# AD5941_testboard.net
KiCad netlist of a schematic drawn in EAGLE
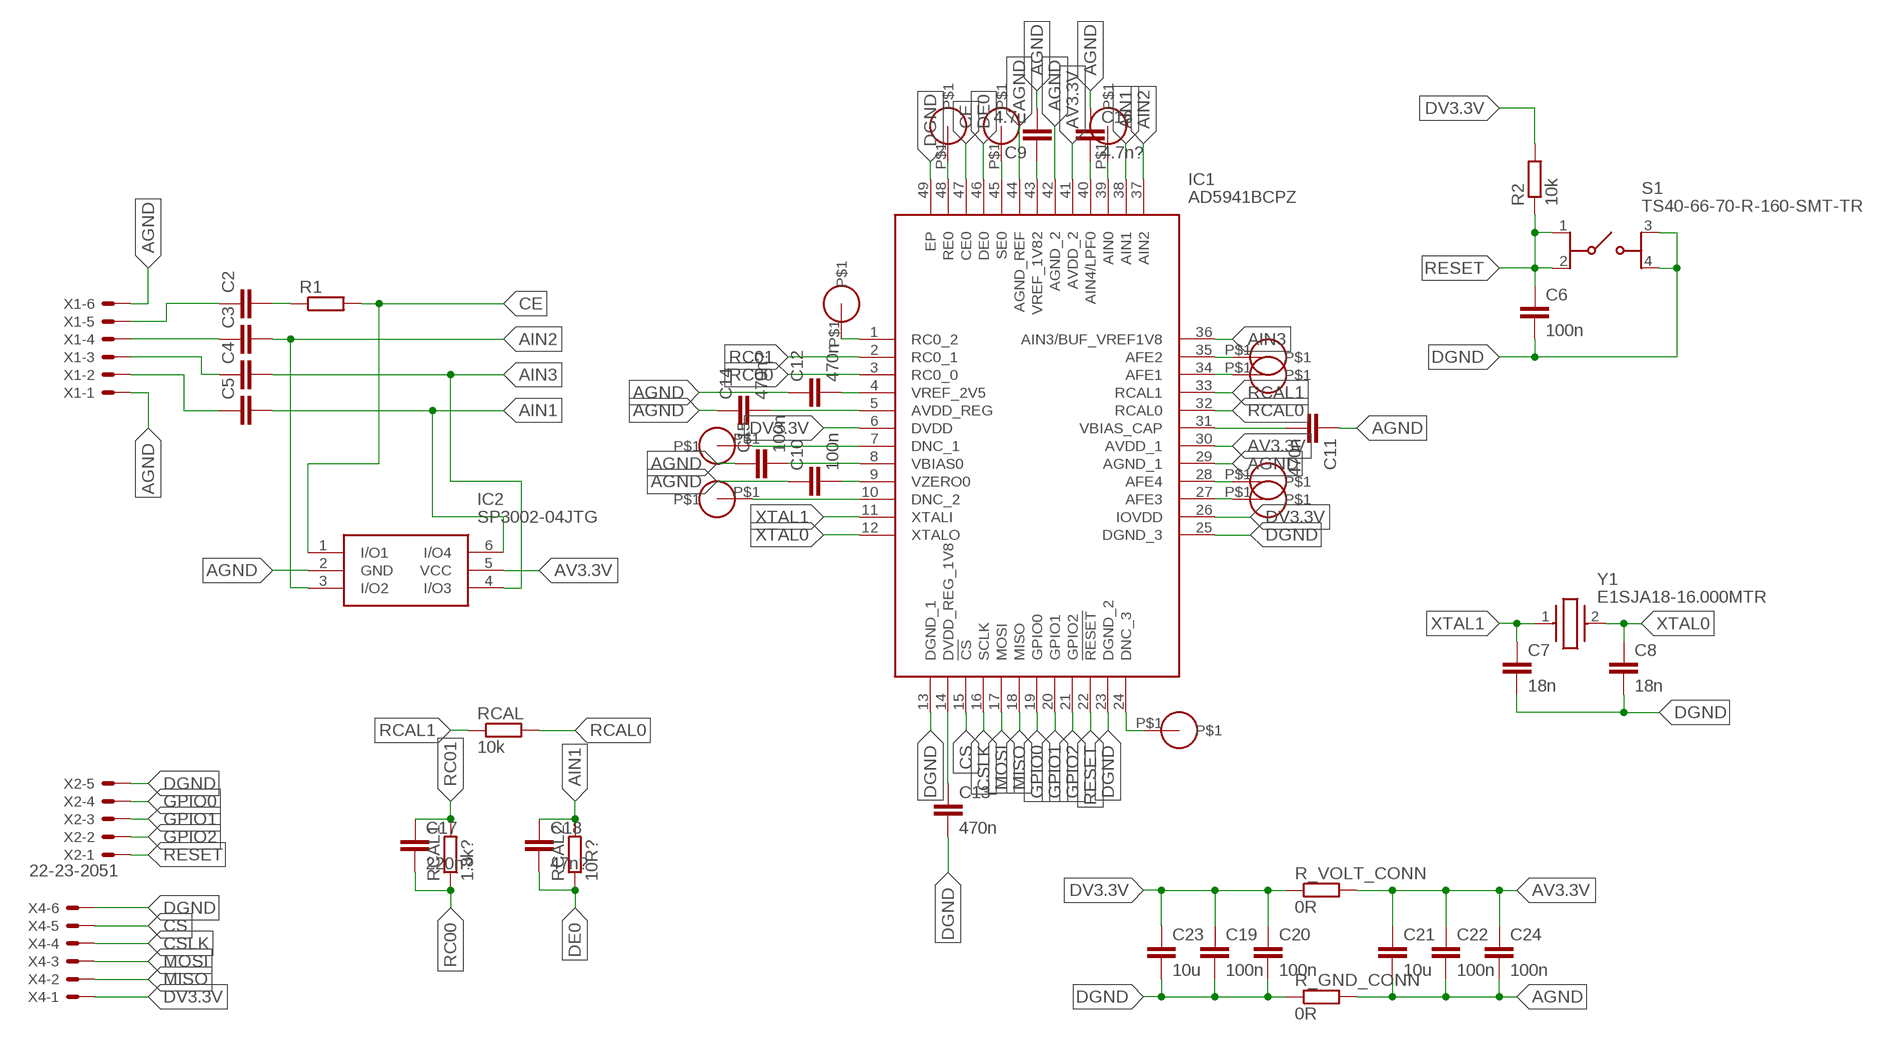
[diagram p0: schematic, sheet 1]

(export (version "E")
  (design (tool "Eeschema 10.0.6"))
  (components
    (comp (ref "C2")
      (value "C-EUC0805")
      (footprint "eagle-import:C0805")
      (libsource (lib "eagle-import") (part "C-EUC0805"))
    )
    (comp (ref "C3")
      (value "C-EUC0805")
      (footprint "eagle-import:C0805")
      (libsource (lib "eagle-import") (part "C-EUC0805"))
    )
    (comp (ref "C4")
      (value "C-EUC0805")
      (footprint "eagle-import:C0805")
      (libsource (lib "eagle-import") (part "C-EUC0805"))
    )
    (comp (ref "C5")
      (value "C-EUC0805")
      (footprint "eagle-import:C0805")
      (libsource (lib "eagle-import") (part "C-EUC0805"))
    )
    (comp (ref "C6")
      (value "100n")
      (footprint "eagle-import:C0805")
      (libsource (lib "eagle-import") (part "C-EUC0805"))
    )
    (comp (ref "C7")
      (value "18n")
      (footprint "eagle-import:C0805")
      (libsource (lib "eagle-import") (part "C-EUC0805"))
    )
    (comp (ref "C8")
      (value "18n")
      (footprint "eagle-import:C0805")
      (libsource (lib "eagle-import") (part "C-EUC0805"))
    )
    (comp (ref "C9")
      (value "4.7u")
      (footprint "eagle-import:C0805")
      (libsource (lib "eagle-import") (part "C-EUC0805"))
    )
    (comp (ref "C10")
      (value "100n")
      (footprint "eagle-import:C0805")
      (libsource (lib "eagle-import") (part "C-EUC0805"))
    )
    (comp (ref "C11")
      (value "470n")
      (footprint "eagle-import:C0805")
      (libsource (lib "eagle-import") (part "C-EUC0805"))
    )
    (comp (ref "C12")
      (value "470n")
      (footprint "eagle-import:C0805")
      (libsource (lib "eagle-import") (part "C-EUC0805"))
    )
    (comp (ref "C13")
      (value "470n")
      (footprint "eagle-import:C0805")
      (libsource (lib "eagle-import") (part "C-EUC0805"))
    )
    (comp (ref "C14")
      (value "470n?")
      (footprint "eagle-import:C0805")
      (libsource (lib "eagle-import") (part "C-EUC0805"))
    )
    (comp (ref "C15")
      (value "100n")
      (footprint "eagle-import:C0805")
      (libsource (lib "eagle-import") (part "C-EUC0805"))
    )
    (comp (ref "C16")
      (value "4.7n?")
      (footprint "eagle-import:C0805")
      (libsource (lib "eagle-import") (part "C-EUC0805"))
    )
    (comp (ref "C17")
      (value "220n?")
      (footprint "eagle-import:C0805")
      (libsource (lib "eagle-import") (part "C-EUC0805"))
    )
    (comp (ref "C18")
      (value "47n?")
      (footprint "eagle-import:C0805")
      (libsource (lib "eagle-import") (part "C-EUC0805"))
    )
    (comp (ref "C19")
      (value "100n")
      (footprint "eagle-import:C0805")
      (libsource (lib "eagle-import") (part "C-EUC0805"))
    )
    (comp (ref "C20")
      (value "100n")
      (footprint "eagle-import:C0805")
      (libsource (lib "eagle-import") (part "C-EUC0805"))
    )
    (comp (ref "C21")
      (value "10u")
      (footprint "eagle-import:C0805")
      (libsource (lib "eagle-import") (part "C-EUC0805"))
    )
    (comp (ref "C22")
      (value "100n")
      (footprint "eagle-import:C0805")
      (libsource (lib "eagle-import") (part "C-EUC0805"))
    )
    (comp (ref "C23")
      (value "10u")
      (footprint "eagle-import:C0805")
      (libsource (lib "eagle-import") (part "C-EUC0805"))
    )
    (comp (ref "C24")
      (value "100n")
      (footprint "eagle-import:C0805")
      (libsource (lib "eagle-import") (part "C-EUC0805"))
    )
    (comp (ref "IC1")
      (value "AD5941BCPZ")
      (footprint "eagle-import:QFN50P700X700X80-49N")
      (fields (field (name "MOUSER_PART_NUMBER") "584-AD5941BCPZ"))
      (libsource (lib "eagle-import") (part "AD5941BCPZ"))
    )
    (comp (ref "IC2")
      (value "SP3002-04JTG")
      (footprint "eagle-import:SOT65P220X110-6N")
      (fields (field (name "MOUSER_PART_NUMBER") "576-SP3002-04JTG"))
      (libsource (lib "eagle-import") (part "SP3002-04JTG"))
    )
    (comp (ref "R1")
      (value "R-EU_R0603")
      (footprint "eagle-import:R0603")
      (libsource (lib "eagle-import") (part "R-EU_R0603"))
    )
    (comp (ref "R2")
      (value "10k")
      (footprint "eagle-import:R0603")
      (libsource (lib "eagle-import") (part "R-EU_R0603"))
    )
    (comp (ref "RCAL")
      (value "10k")
      (footprint "eagle-import:R0603")
      (libsource (lib "eagle-import") (part "R-EU_R0603"))
    )
    (comp (ref "RCAL1")
      (value "1.8k?")
      (footprint "eagle-import:R0603")
      (libsource (lib "eagle-import") (part "R-EU_R0603"))
    )
    (comp (ref "RCAL2")
      (value "10R?")
      (footprint "eagle-import:R0603")
      (libsource (lib "eagle-import") (part "R-EU_R0603"))
    )
    (comp (ref "R_GND_CONN")
      (value "0R")
      (footprint "eagle-import:R0603")
      (libsource (lib "eagle-import") (part "R-EU_R0603"))
    )
    (comp (ref "R_VOLT_CONN")
      (value "0R")
      (footprint "eagle-import:R0603")
      (libsource (lib "eagle-import") (part "R-EU_R0603"))
    )
    (comp (ref "S1")
      (value "TS40-66-70-R-160-SMT-TR")
      (footprint "eagle-import:TS406670R160SMTTR")
      (libsource (lib "eagle-import") (part "TS40-66-70-R-160-SMT-TR"))
    )
    (comp (ref "U$1")
      (value "1XPIN+HOLE")
      (footprint "eagle-import:1XPIN+HOLE")
      (libsource (lib "eagle-import") (part "1XPIN+HOLE"))
    )
    (comp (ref "U$2")
      (value "1XPIN+HOLE")
      (footprint "eagle-import:1XPIN+HOLE")
      (libsource (lib "eagle-import") (part "1XPIN+HOLE"))
    )
    (comp (ref "U$3")
      (value "1XPIN+HOLE")
      (footprint "eagle-import:1XPIN+HOLE")
      (libsource (lib "eagle-import") (part "1XPIN+HOLE"))
    )
    (comp (ref "U$4")
      (value "1XPIN+HOLE")
      (footprint "eagle-import:1XPIN+HOLE")
      (libsource (lib "eagle-import") (part "1XPIN+HOLE"))
    )
    (comp (ref "U$5")
      (value "1XPIN+HOLE")
      (footprint "eagle-import:1XPIN+HOLE")
      (libsource (lib "eagle-import") (part "1XPIN+HOLE"))
    )
    (comp (ref "U$6")
      (value "1XPIN+HOLE")
      (footprint "eagle-import:1XPIN+HOLE")
      (libsource (lib "eagle-import") (part "1XPIN+HOLE"))
    )
    (comp (ref "U$7")
      (value "1XPIN+HOLE")
      (footprint "eagle-import:1XPIN+HOLE")
      (libsource (lib "eagle-import") (part "1XPIN+HOLE"))
    )
    (comp (ref "U$8")
      (value "1XPIN+HOLE")
      (footprint "eagle-import:1XPIN+HOLE")
      (libsource (lib "eagle-import") (part "1XPIN+HOLE"))
    )
    (comp (ref "U$9")
      (value "1XPIN+HOLE")
      (footprint "eagle-import:1XPIN+HOLE")
      (libsource (lib "eagle-import") (part "1XPIN+HOLE"))
    )
    (comp (ref "U$10")
      (value "1XPIN+HOLE")
      (footprint "eagle-import:1XPIN+HOLE")
      (libsource (lib "eagle-import") (part "1XPIN+HOLE"))
    )
    (comp (ref "U$11")
      (value "1XPIN+HOLE")
      (footprint "eagle-import:1XPIN+HOLE")
      (libsource (lib "eagle-import") (part "1XPIN+HOLE"))
    )
    (comp (ref "X1")
      (value "22-23-2061")
      (footprint "eagle-import:22-23-2061")
      (fields (field (name "MF") "MOLEX"))
      (libsource (lib "eagle-import") (part "22-23-2061"))
    )
    (comp (ref "X2")
      (value "22-23-2051")
      (footprint "eagle-import:22-23-2051")
      (fields (field (name "MF") "MOLEX"))
      (libsource (lib "eagle-import") (part "22-23-2051"))
    )
    (comp (ref "X4")
      (value "22-23-2061")
      (footprint "eagle-import:22-23-2061")
      (fields (field (name "MF") "MOLEX"))
      (libsource (lib "eagle-import") (part "22-23-2061"))
    )
    (comp (ref "Y1")
      (value "E1SJA18-16.000MTR")
      (footprint "eagle-import:E1SJA1816000MTR")
      (fields (field (name "MOUSER_PART_NUMBER") "815-E1SJA1816000MTR"))
      (libsource (lib "eagle-import") (part "E1SJA18-16.000MTR"))
    )
  )
  (nets
    (net (code "1") (name "AGND") (class "Default")
      (node (ref "C10") (pin "1") (pinfunction "1_1") (pintype "passive"))
      (node (ref "C11") (pin "1") (pinfunction "1_1") (pintype "passive"))
      (node (ref "C12") (pin "1") (pinfunction "1_1") (pintype "passive"))
      (node (ref "C14") (pin "1") (pinfunction "1_1") (pintype "passive"))
      (node (ref "C15") (pin "1") (pinfunction "1_1") (pintype "passive"))
      (node (ref "C16") (pin "1") (pinfunction "1_1") (pintype "passive"))
      (node (ref "C21") (pin "2") (pinfunction "2_2") (pintype "passive"))
      (node (ref "C22") (pin "2") (pinfunction "2_2") (pintype "passive"))
      (node (ref "C24") (pin "2") (pinfunction "2_2") (pintype "passive"))
      (node (ref "C9") (pin "2") (pinfunction "2_2") (pintype "passive"))
      (node (ref "IC1") (pin "29") (pinfunction "AGND_1_29") (pintype "bidirectional"))
      (node (ref "IC1") (pin "42") (pinfunction "AGND_2_42") (pintype "bidirectional"))
      (node (ref "IC1") (pin "44") (pinfunction "AGND_REF_44") (pintype "bidirectional"))
      (node (ref "IC2") (pin "2") (pinfunction "GND_2") (pintype "bidirectional"))
      (node (ref "R_GND_CONN") (pin "2") (pinfunction "2_2") (pintype "passive"))
      (node (ref "X1") (pin "1") (pinfunction "S_1") (pintype "passive"))
      (node (ref "X1") (pin "6") (pinfunction "S_6") (pintype "passive"))
    )
    (net (code "2") (name "AIN1") (class "Default")
      (node (ref "C18") (pin "1") (pinfunction "1_1") (pintype "passive"))
      (node (ref "C5") (pin "2") (pinfunction "2_2") (pintype "passive"))
      (node (ref "IC1") (pin "38") (pinfunction "AIN1_38") (pintype "bidirectional"))
      (node (ref "IC2") (pin "6") (pinfunction "I/O4_6") (pintype "bidirectional"))
      (node (ref "RCAL2") (pin "2") (pinfunction "2_2") (pintype "passive"))
    )
    (net (code "3") (name "AIN2") (class "Default")
      (node (ref "C3") (pin "2") (pinfunction "2_2") (pintype "passive"))
      (node (ref "IC1") (pin "37") (pinfunction "AIN2_37") (pintype "bidirectional"))
      (node (ref "IC2") (pin "3") (pinfunction "I/O2_3") (pintype "bidirectional"))
    )
    (net (code "4") (name "AIN3") (class "Default")
      (node (ref "C4") (pin "2") (pinfunction "2_2") (pintype "passive"))
      (node (ref "IC1") (pin "36") (pinfunction "AIN3/BUF_VREF1V8_36") (pintype "bidirectional"))
      (node (ref "IC2") (pin "4") (pinfunction "I/O3_4") (pintype "bidirectional"))
    )
    (net (code "5") (name "AV3.3V") (class "Default")
      (node (ref "C21") (pin "1") (pinfunction "1_1") (pintype "passive"))
      (node (ref "C22") (pin "1") (pinfunction "1_1") (pintype "passive"))
      (node (ref "C24") (pin "1") (pinfunction "1_1") (pintype "passive"))
      (node (ref "IC1") (pin "30") (pinfunction "AVDD_1_30") (pintype "bidirectional"))
      (node (ref "IC1") (pin "41") (pinfunction "AVDD_2_41") (pintype "bidirectional"))
      (node (ref "IC2") (pin "5") (pinfunction "VCC_5") (pintype "bidirectional"))
      (node (ref "R_VOLT_CONN") (pin "2") (pinfunction "2_2") (pintype "passive"))
    )
    (net (code "6") (name "CE") (class "Default")
      (node (ref "IC1") (pin "47") (pinfunction "CE0_47") (pintype "bidirectional"))
      (node (ref "IC2") (pin "1") (pinfunction "I/O1_1") (pintype "bidirectional"))
      (node (ref "R1") (pin "2") (pinfunction "2_2") (pintype "passive"))
    )
    (net (code "7") (name "CS") (class "Default")
      (node (ref "IC1") (pin "15") (pinfunction "~{CS}_15") (pintype "bidirectional"))
      (node (ref "X4") (pin "5") (pinfunction "S_5") (pintype "passive"))
    )
    (net (code "8") (name "CSLK") (class "Default")
      (node (ref "IC1") (pin "16") (pinfunction "SCLK_16") (pintype "bidirectional"))
      (node (ref "X4") (pin "4") (pinfunction "S_4") (pintype "passive"))
    )
    (net (code "9") (name "DE0") (class "Default")
      (node (ref "C18") (pin "2") (pinfunction "2_2") (pintype "passive"))
      (node (ref "IC1") (pin "46") (pinfunction "DE0_46") (pintype "bidirectional"))
      (node (ref "RCAL2") (pin "1") (pinfunction "1_1") (pintype "passive"))
    )
    (net (code "10") (name "DGND") (class "Default")
      (node (ref "C13") (pin "2") (pinfunction "2_2") (pintype "passive"))
      (node (ref "C19") (pin "2") (pinfunction "2_2") (pintype "passive"))
      (node (ref "C20") (pin "2") (pinfunction "2_2") (pintype "passive"))
      (node (ref "C23") (pin "2") (pinfunction "2_2") (pintype "passive"))
      (node (ref "C6") (pin "2") (pinfunction "2_2") (pintype "passive"))
      (node (ref "C7") (pin "2") (pinfunction "2_2") (pintype "passive"))
      (node (ref "C8") (pin "2") (pinfunction "2_2") (pintype "passive"))
      (node (ref "IC1") (pin "13") (pinfunction "DGND_1_13") (pintype "bidirectional"))
      (node (ref "IC1") (pin "23") (pinfunction "DGND_2_23") (pintype "bidirectional"))
      (node (ref "IC1") (pin "25") (pinfunction "DGND_3_25") (pintype "bidirectional"))
      (node (ref "IC1") (pin "49") (pinfunction "EP_49") (pintype "bidirectional"))
      (node (ref "R_GND_CONN") (pin "1") (pinfunction "1_1") (pintype "passive"))
      (node (ref "S1") (pin "3") (pinfunction "NO_1_3") (pintype "bidirectional"))
      (node (ref "S1") (pin "4") (pinfunction "NO_2_4") (pintype "bidirectional"))
      (node (ref "X2") (pin "5") (pinfunction "S_5") (pintype "passive"))
      (node (ref "X4") (pin "6") (pinfunction "S_6") (pintype "passive"))
    )
    (net (code "11") (name "DV3.3V") (class "Default")
      (node (ref "C19") (pin "1") (pinfunction "1_1") (pintype "passive"))
      (node (ref "C20") (pin "1") (pinfunction "1_1") (pintype "passive"))
      (node (ref "C23") (pin "1") (pinfunction "1_1") (pintype "passive"))
      (node (ref "IC1") (pin "26") (pinfunction "IOVDD_26") (pintype "bidirectional"))
      (node (ref "IC1") (pin "6") (pinfunction "DVDD_6") (pintype "bidirectional"))
      (node (ref "R2") (pin "2") (pinfunction "2_2") (pintype "passive"))
      (node (ref "R_VOLT_CONN") (pin "1") (pinfunction "1_1") (pintype "passive"))
      (node (ref "X4") (pin "1") (pinfunction "S_1") (pintype "passive"))
    )
    (net (code "12") (name "GPIO0") (class "Default")
      (node (ref "IC1") (pin "19") (pinfunction "GPIO0_19") (pintype "bidirectional"))
      (node (ref "X2") (pin "4") (pinfunction "S_4") (pintype "passive"))
    )
    (net (code "13") (name "GPIO1") (class "Default")
      (node (ref "IC1") (pin "20") (pinfunction "GPIO1_20") (pintype "bidirectional"))
      (node (ref "X2") (pin "3") (pinfunction "S_3") (pintype "passive"))
    )
    (net (code "14") (name "GPIO2") (class "Default")
      (node (ref "IC1") (pin "21") (pinfunction "GPIO2_21") (pintype "bidirectional"))
      (node (ref "X2") (pin "2") (pinfunction "S_2") (pintype "passive"))
    )
    (net (code "15") (name "MISO") (class "Default")
      (node (ref "IC1") (pin "18") (pinfunction "MISO_18") (pintype "bidirectional"))
      (node (ref "X4") (pin "2") (pinfunction "S_2") (pintype "passive"))
    )
    (net (code "16") (name "MOSI") (class "Default")
      (node (ref "IC1") (pin "17") (pinfunction "MOSI_17") (pintype "bidirectional"))
      (node (ref "X4") (pin "3") (pinfunction "S_3") (pintype "passive"))
    )
    (net (code "17") (name "Net-(C2-Pad2)") (class "Default")
      (node (ref "C2") (pin "2") (pinfunction "2_2") (pintype "passive"))
      (node (ref "R1") (pin "1") (pinfunction "1_1") (pintype "passive"))
    )
    (net (code "18") (name "Net-(IC1-AFE1)") (class "Default")
      (node (ref "IC1") (pin "34") (pinfunction "AFE1_34") (pintype "bidirectional"))
      (node (ref "U$8") (pin "P$1") (pinfunction "P$1_P$1") (pintype "bidirectional"))
    )
    (net (code "19") (name "Net-(IC1-AFE2)") (class "Default")
      (node (ref "IC1") (pin "35") (pinfunction "AFE2_35") (pintype "bidirectional"))
      (node (ref "U$7") (pin "P$1") (pinfunction "P$1_P$1") (pintype "bidirectional"))
    )
    (net (code "20") (name "Net-(IC1-AFE3)") (class "Default")
      (node (ref "IC1") (pin "27") (pinfunction "AFE3_27") (pintype "bidirectional"))
      (node (ref "U$9") (pin "P$1") (pinfunction "P$1_P$1") (pintype "bidirectional"))
    )
    (net (code "21") (name "Net-(IC1-AFE4)") (class "Default")
      (node (ref "IC1") (pin "28") (pinfunction "AFE4_28") (pintype "bidirectional"))
      (node (ref "U$10") (pin "P$1") (pinfunction "P$1_P$1") (pintype "bidirectional"))
    )
    (net (code "22") (name "Net-(IC1-AIN0)") (class "Default")
      (node (ref "IC1") (pin "39") (pinfunction "AIN0_39") (pintype "bidirectional"))
      (node (ref "U$6") (pin "P$1") (pinfunction "P$1_P$1") (pintype "bidirectional"))
    )
    (net (code "23") (name "Net-(IC1-AIN4{slash}LPF0)") (class "Default")
      (node (ref "C16") (pin "2") (pinfunction "2_2") (pintype "passive"))
      (node (ref "IC1") (pin "40") (pinfunction "AIN4/LPF0_40") (pintype "bidirectional"))
    )
    (net (code "24") (name "Net-(IC1-AVDD_REG)") (class "Default")
      (node (ref "C14") (pin "2") (pinfunction "2_2") (pintype "passive"))
      (node (ref "IC1") (pin "5") (pinfunction "AVDD_REG_5") (pintype "bidirectional"))
    )
    (net (code "25") (name "Net-(IC1-DNC_1)") (class "Default")
      (node (ref "IC1") (pin "7") (pinfunction "DNC_1_7") (pintype "bidirectional"))
      (node (ref "U$11") (pin "P$1") (pinfunction "P$1_P$1") (pintype "bidirectional"))
    )
    (net (code "26") (name "Net-(IC1-DNC_2)") (class "Default")
      (node (ref "IC1") (pin "10") (pinfunction "DNC_2_10") (pintype "bidirectional"))
      (node (ref "U$3") (pin "P$1") (pinfunction "P$1_P$1") (pintype "bidirectional"))
    )
    (net (code "27") (name "Net-(IC1-DNC_3)") (class "Default")
      (node (ref "IC1") (pin "24") (pinfunction "DNC_3_24") (pintype "bidirectional"))
      (node (ref "U$1") (pin "P$1") (pinfunction "P$1_P$1") (pintype "bidirectional"))
    )
    (net (code "28") (name "Net-(IC1-DVDD_REG_1V8)") (class "Default")
      (node (ref "C13") (pin "1") (pinfunction "1_1") (pintype "passive"))
      (node (ref "IC1") (pin "14") (pinfunction "DVDD_REG_1V8_14") (pintype "bidirectional"))
    )
    (net (code "29") (name "Net-(IC1-RC0_2)") (class "Default")
      (node (ref "IC1") (pin "1") (pinfunction "RC0_2_1") (pintype "bidirectional"))
      (node (ref "U$2") (pin "P$1") (pinfunction "P$1_P$1") (pintype "bidirectional"))
    )
    (net (code "30") (name "Net-(IC1-RE0)") (class "Default")
      (node (ref "IC1") (pin "48") (pinfunction "RE0_48") (pintype "bidirectional"))
      (node (ref "U$4") (pin "P$1") (pinfunction "P$1_P$1") (pintype "bidirectional"))
    )
    (net (code "31") (name "Net-(IC1-SE0)") (class "Default")
      (node (ref "IC1") (pin "45") (pinfunction "SE0_45") (pintype "bidirectional"))
      (node (ref "U$5") (pin "P$1") (pinfunction "P$1_P$1") (pintype "bidirectional"))
    )
    (net (code "32") (name "Net-(IC1-VBIAS0)") (class "Default")
      (node (ref "C15") (pin "2") (pinfunction "2_2") (pintype "passive"))
      (node (ref "IC1") (pin "8") (pinfunction "VBIAS0_8") (pintype "bidirectional"))
    )
    (net (code "33") (name "Net-(IC1-VBIAS_CAP)") (class "Default")
      (node (ref "C11") (pin "2") (pinfunction "2_2") (pintype "passive"))
      (node (ref "IC1") (pin "31") (pinfunction "VBIAS_CAP_31") (pintype "bidirectional"))
    )
    (net (code "34") (name "Net-(IC1-VREF_1V82)") (class "Default")
      (node (ref "C9") (pin "1") (pinfunction "1_1") (pintype "passive"))
      (node (ref "IC1") (pin "43") (pinfunction "VREF_1V82_43") (pintype "bidirectional"))
    )
    (net (code "35") (name "Net-(IC1-VREF_2V5)") (class "Default")
      (node (ref "C12") (pin "2") (pinfunction "2_2") (pintype "passive"))
      (node (ref "IC1") (pin "4") (pinfunction "VREF_2V5_4") (pintype "bidirectional"))
    )
    (net (code "36") (name "Net-(IC1-VZERO0)") (class "Default")
      (node (ref "C10") (pin "2") (pinfunction "2_2") (pintype "passive"))
      (node (ref "IC1") (pin "9") (pinfunction "VZERO0_9") (pintype "bidirectional"))
    )
    (net (code "37") (name "Net-(X1B-S)") (class "Default")
      (node (ref "C5") (pin "1") (pinfunction "1_1") (pintype "passive"))
      (node (ref "X1") (pin "2") (pinfunction "S_2") (pintype "passive"))
    )
    (net (code "38") (name "Net-(X1C-S)") (class "Default")
      (node (ref "C4") (pin "1") (pinfunction "1_1") (pintype "passive"))
      (node (ref "X1") (pin "3") (pinfunction "S_3") (pintype "passive"))
    )
    (net (code "39") (name "Net-(X1D-S)") (class "Default")
      (node (ref "C3") (pin "1") (pinfunction "1_1") (pintype "passive"))
      (node (ref "X1") (pin "4") (pinfunction "S_4") (pintype "passive"))
    )
    (net (code "40") (name "Net-(X1E-S)") (class "Default")
      (node (ref "C2") (pin "1") (pinfunction "1_1") (pintype "passive"))
      (node (ref "X1") (pin "5") (pinfunction "S_5") (pintype "passive"))
    )
    (net (code "41") (name "RC00") (class "Default")
      (node (ref "C17") (pin "2") (pinfunction "2_2") (pintype "passive"))
      (node (ref "IC1") (pin "3") (pinfunction "RC0_0_3") (pintype "bidirectional"))
      (node (ref "RCAL1") (pin "1") (pinfunction "1_1") (pintype "passive"))
    )
    (net (code "42") (name "RC01") (class "Default")
      (node (ref "C17") (pin "1") (pinfunction "1_1") (pintype "passive"))
      (node (ref "IC1") (pin "2") (pinfunction "RC0_1_2") (pintype "bidirectional"))
      (node (ref "RCAL1") (pin "2") (pinfunction "2_2") (pintype "passive"))
    )
    (net (code "43") (name "RCAL0") (class "Default")
      (node (ref "IC1") (pin "32") (pinfunction "RCAL0_32") (pintype "bidirectional"))
      (node (ref "RCAL") (pin "2") (pinfunction "2_2") (pintype "passive"))
    )
    (net (code "44") (name "RCAL1") (class "Default")
      (node (ref "IC1") (pin "33") (pinfunction "RCAL1_33") (pintype "bidirectional"))
      (node (ref "RCAL") (pin "1") (pinfunction "1_1") (pintype "passive"))
    )
    (net (code "45") (name "RESET") (class "Default")
      (node (ref "C6") (pin "1") (pinfunction "1_1") (pintype "passive"))
      (node (ref "IC1") (pin "22") (pinfunction "~{RESET}_22") (pintype "bidirectional"))
      (node (ref "R2") (pin "1") (pinfunction "1_1") (pintype "passive"))
      (node (ref "S1") (pin "1") (pinfunction "COM_1_1") (pintype "bidirectional"))
      (node (ref "S1") (pin "2") (pinfunction "COM_2_2") (pintype "bidirectional"))
      (node (ref "X2") (pin "1") (pinfunction "S_1") (pintype "passive"))
    )
    (net (code "46") (name "XTAL0") (class "Default")
      (node (ref "C8") (pin "1") (pinfunction "1_1") (pintype "passive"))
      (node (ref "IC1") (pin "12") (pinfunction "XTALO_12") (pintype "bidirectional"))
      (node (ref "Y1") (pin "2") (pinfunction "2_2") (pintype "bidirectional"))
    )
    (net (code "47") (name "XTAL1") (class "Default")
      (node (ref "C7") (pin "1") (pinfunction "1_1") (pintype "passive"))
      (node (ref "IC1") (pin "11") (pinfunction "XTALI_11") (pintype "bidirectional"))
      (node (ref "Y1") (pin "1") (pinfunction "1_1") (pintype "bidirectional"))
    )
  )
)
